# 08_BB_Processor.net
KiCad netlist of a schematic drawn in Altium Designer
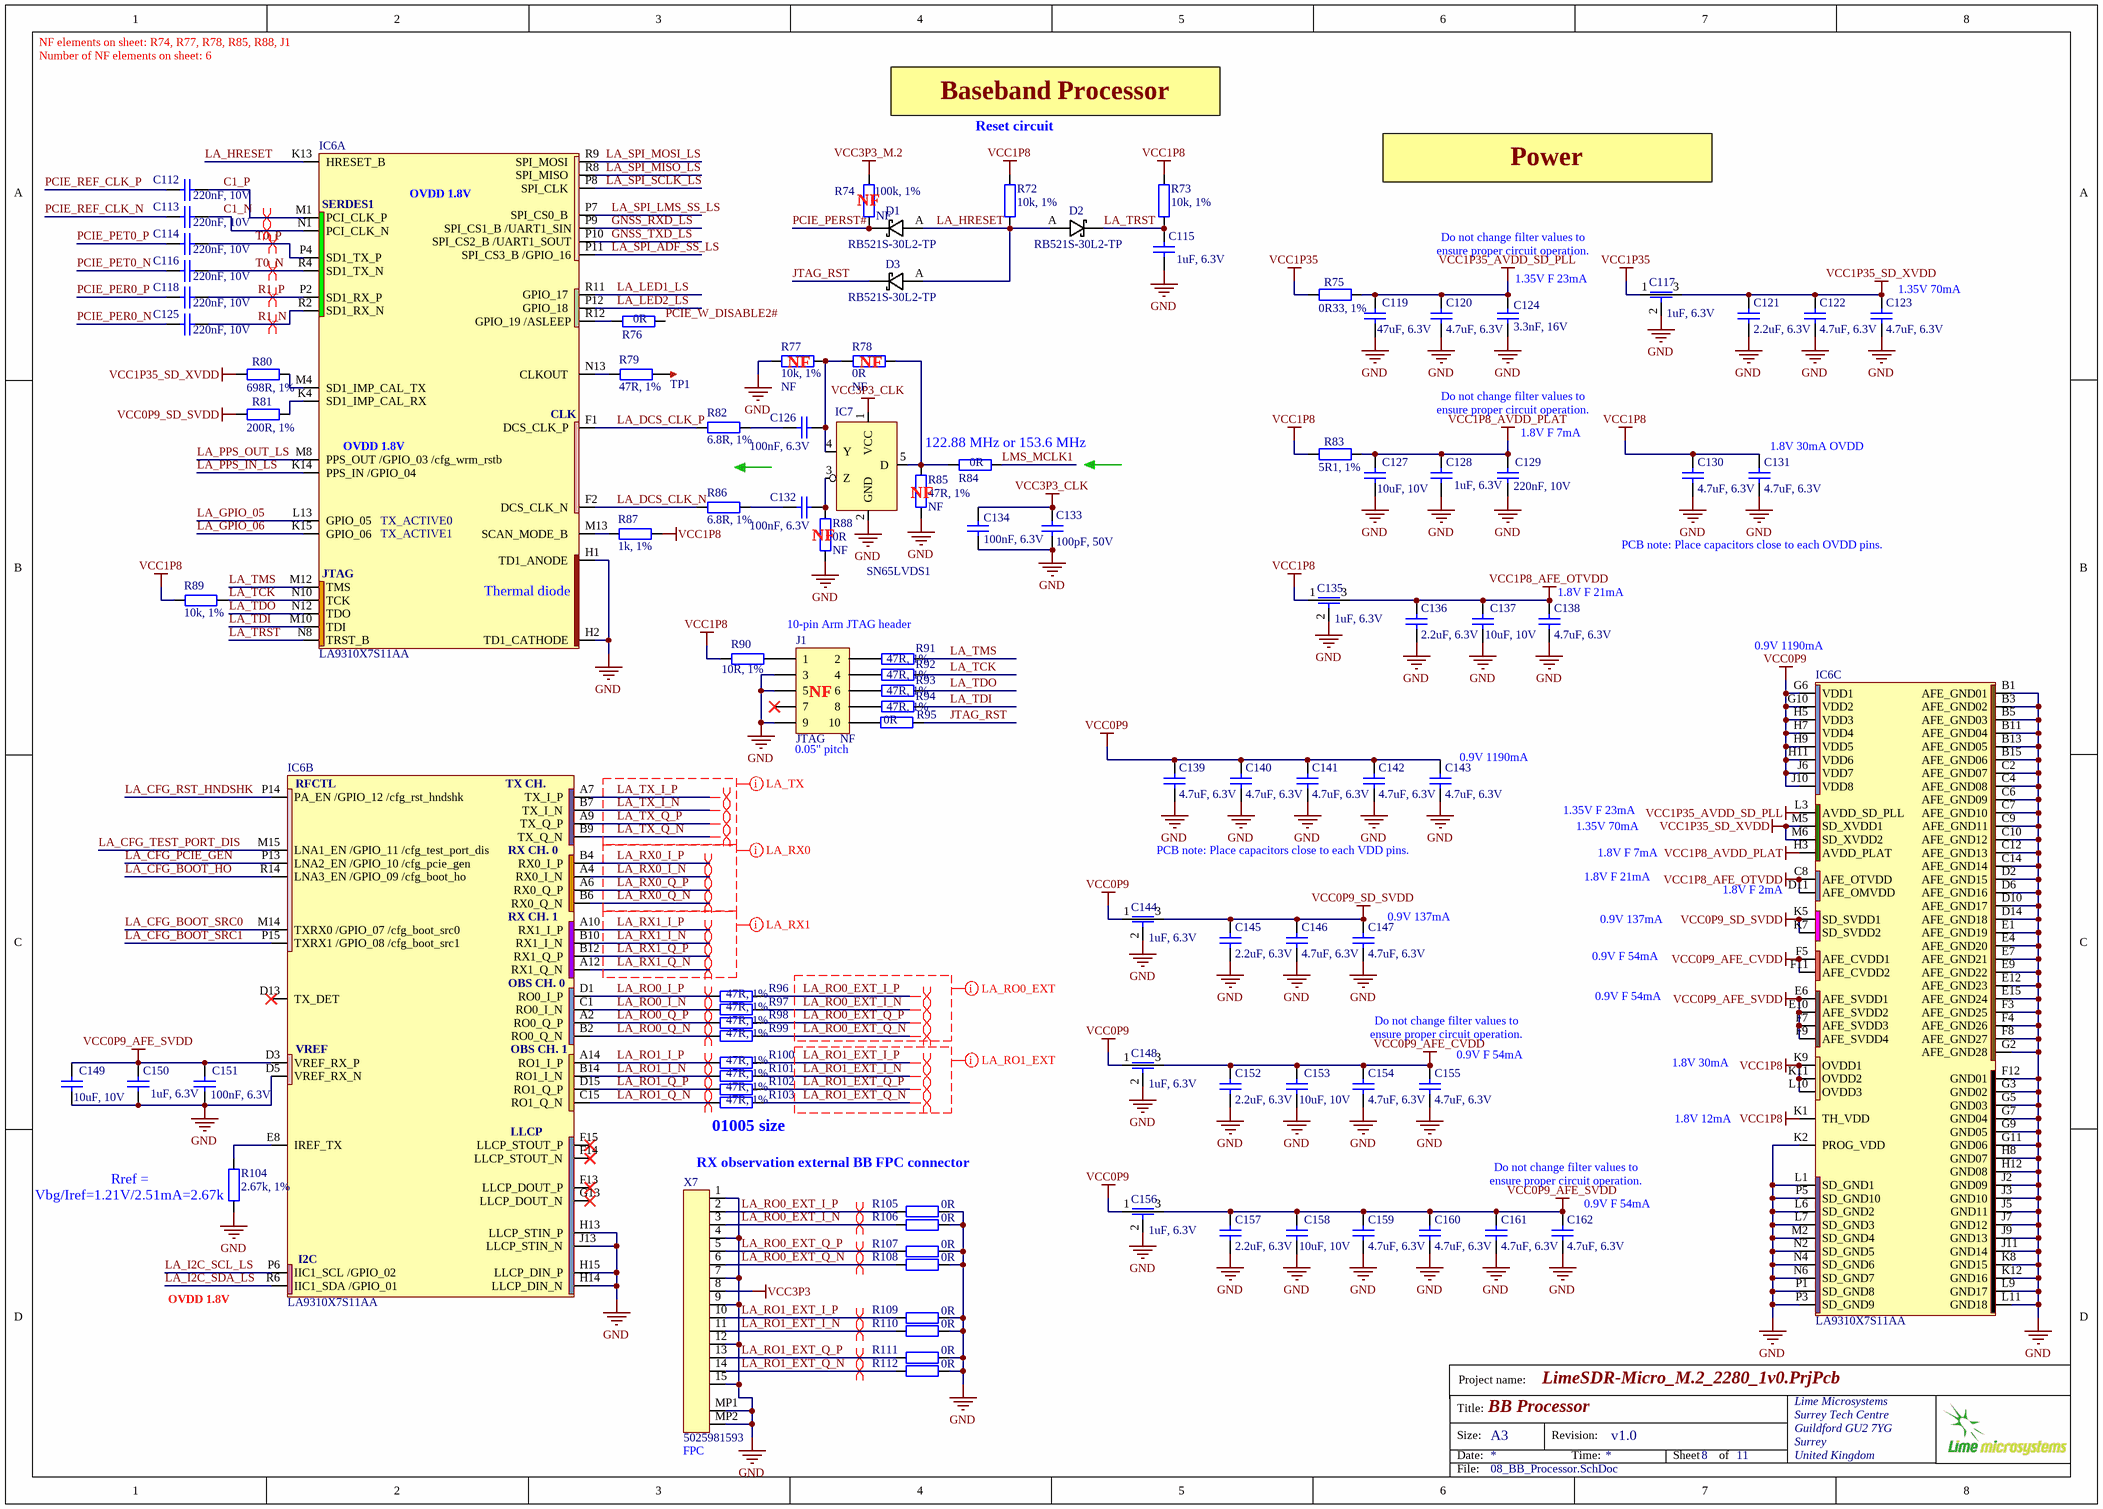
[diagram p0: 08_BB_Processor.SchDoc]

(export (version "E")
  (design (tool "Eeschema 10.0.6"))
  (components
    (comp (ref "C112")
      (value "220nF, 10V")
      (footprint "CAP0201")
      (fields
        (field (name "MANUFACTURER") "Murata")
        (field (name "TOLERANCE") "20%")
        (field (name "VOLTAGE") "10V")
      )
      (libsource (lib "LimeMicroAltiumLib_schLib") (part "Cap_0402"))
    )
    (comp (ref "C113")
      (value "220nF, 10V")
      (footprint "CAP0201")
      (fields
        (field (name "MANUFACTURER") "Murata")
        (field (name "TOLERANCE") "20%")
        (field (name "VOLTAGE") "10V")
      )
      (libsource (lib "LimeMicroAltiumLib_schLib") (part "Cap_0402"))
    )
    (comp (ref "C114")
      (value "220nF, 10V")
      (footprint "CAP0201")
      (fields
        (field (name "MANUFACTURER") "Murata")
        (field (name "TOLERANCE") "20%")
        (field (name "VOLTAGE") "10V")
      )
      (libsource (lib "LimeMicroAltiumLib_schLib") (part "Cap_0402"))
    )
    (comp (ref "C115")
      (value "1uF, 6.3V")
      (footprint "CAP0201")
      (fields (field (name "TOLERANCE") "±20%") (field (name "MANUFACTURER") "TDK Corporation"))
      (libsource (lib "LimeMicroAltiumLib_schLib") (part "Cap_0402"))
    )
    (comp (ref "C116")
      (value "220nF, 10V")
      (footprint "CAP0201")
      (fields
        (field (name "MANUFACTURER") "Murata")
        (field (name "TOLERANCE") "20%")
        (field (name "VOLTAGE") "10V")
      )
      (libsource (lib "LimeMicroAltiumLib_schLib") (part "Cap_0402"))
    )
    (comp (ref "C117")
      (value "1uF, 6.3V")
      (footprint "CAP0603_FEEDTHROUGH")
      (fields (field (name "MANUFACTURER") "TDK"))
      (libsource (lib "LimeMicroAltiumLib_schLib_r01") (part "Cap_feed_through"))
    )
    (comp (ref "C118")
      (value "220nF, 10V")
      (footprint "CAP0201")
      (fields
        (field (name "MANUFACTURER") "Murata")
        (field (name "TOLERANCE") "20%")
        (field (name "VOLTAGE") "10V")
      )
      (libsource (lib "LimeMicroAltiumLib_schLib") (part "Cap_0402"))
    )
    (comp (ref "C119")
      (value "47uF, 6.3V")
      (footprint "CAP0603")
      (fields (field (name "MANUFACTURER") "Murata") (field (name "TOLERANCE") "20%"))
      (libsource (lib "LimeFPGAboard_schLib") (part "Cap_0603"))
    )
    (comp (ref "C120")
      (value "4.7uF, 6.3V")
      (footprint "CAP0201")
      (fields (field (name "MANUFACTURER") "Murata") (field (name "TOLERANCE") "20%"))
      (libsource (lib "LimeMicroAltiumLib_schLib") (part "Cap_0402"))
    )
    (comp (ref "C121")
      (value "2.2uF, 6.3V")
      (footprint "CAP0201")
      (fields (field (name "MANUFACTURER") "Murata") (field (name "TOLERANCE") "20%"))
      (libsource (lib "LimeMicroAltiumLib_schLib") (part "Cap_0402"))
    )
    (comp (ref "C122")
      (value "4.7uF, 6.3V")
      (footprint "CAP0201")
      (fields (field (name "MANUFACTURER") "Murata") (field (name "TOLERANCE") "20%"))
      (libsource (lib "LimeMicroAltiumLib_schLib") (part "Cap_0402"))
    )
    (comp (ref "C123")
      (value "4.7uF, 6.3V")
      (footprint "CAP0201")
      (fields (field (name "MANUFACTURER") "Murata") (field (name "TOLERANCE") "20%"))
      (libsource (lib "LimeMicroAltiumLib_schLib") (part "Cap_0402"))
    )
    (comp (ref "C124")
      (value "3.3nF, 16V")
      (footprint "CAP0201")
      (fields (field (name "MANUFACTURER") "Murata"))
      (libsource (lib "LimeMicroAltiumLib_schLib") (part "Cap_0402"))
    )
    (comp (ref "C125")
      (value "220nF, 10V")
      (footprint "CAP0201")
      (fields
        (field (name "MANUFACTURER") "Murata")
        (field (name "TOLERANCE") "20%")
        (field (name "VOLTAGE") "10V")
      )
      (libsource (lib "LimeMicroAltiumLib_schLib") (part "Cap_0402"))
    )
    (comp (ref "C126")
      (value "100nF, 6.3V")
      (footprint "CAP0201")
      (fields (field (name "MANUFACTURER") "Samsung") (field (name "TOLERANCE") "20%"))
      (libsource (lib "LimeMicroAltiumLib_schLib") (part "Cap_0402"))
    )
    (comp (ref "C127")
      (value "10uF, 10V")
      (footprint "CAP0402")
      (fields (field (name "MANUFACTURER") "Murata"))
      (libsource (lib "LimeFPGAboard_schLib") (part "Cap_0603"))
    )
    (comp (ref "C128")
      (value "1uF, 6.3V")
      (footprint "CAP0201")
      (fields (field (name "TOLERANCE") "±20%") (field (name "MANUFACTURER") "TDK Corporation"))
      (libsource (lib "LimeMicroAltiumLib_schLib") (part "Cap_0402"))
    )
    (comp (ref "C129")
      (value "220nF, 10V")
      (footprint "CAP0201")
      (fields
        (field (name "MANUFACTURER") "Murata")
        (field (name "TOLERANCE") "20%")
        (field (name "VOLTAGE") "10V")
      )
      (libsource (lib "LimeMicroAltiumLib_schLib") (part "Cap_0402"))
    )
    (comp (ref "C130")
      (value "4.7uF, 6.3V")
      (footprint "CAP0201")
      (fields (field (name "MANUFACTURER") "Murata") (field (name "TOLERANCE") "20%"))
      (libsource (lib "LimeMicroAltiumLib_schLib") (part "Cap_0402"))
    )
    (comp (ref "C131")
      (value "4.7uF, 6.3V")
      (footprint "CAP0201")
      (fields (field (name "MANUFACTURER") "Murata") (field (name "TOLERANCE") "20%"))
      (libsource (lib "LimeMicroAltiumLib_schLib") (part "Cap_0402"))
    )
    (comp (ref "C132")
      (value "100nF, 6.3V")
      (footprint "CAP0201")
      (fields (field (name "MANUFACTURER") "Samsung") (field (name "TOLERANCE") "20%"))
      (libsource (lib "LimeMicroAltiumLib_schLib") (part "Cap_0402"))
    )
    (comp (ref "C133")
      (value "100pF, 50V")
      (footprint "CAP0201")
      (fields
        (field (name "MANUFACTURER") "TDK")
        (field (name "TOLERANCE") "5%")
        (field (name "VOLTAGE") "50V")
      )
      (libsource (lib "LimeMicroAltiumLib_schLib") (part "Cap_0402"))
    )
    (comp (ref "C134")
      (value "100nF, 6.3V")
      (footprint "CAP0201")
      (fields (field (name "MANUFACTURER") "Samsung") (field (name "TOLERANCE") "20%"))
      (libsource (lib "LimeMicroAltiumLib_schLib") (part "Cap_0402"))
    )
    (comp (ref "C135")
      (value "1uF, 6.3V")
      (footprint "CAP0603_FEEDTHROUGH")
      (fields (field (name "MANUFACTURER") "TDK"))
      (libsource (lib "LimeMicroAltiumLib_schLib_r01") (part "Cap_feed_through"))
    )
    (comp (ref "C136")
      (value "2.2uF, 6.3V")
      (footprint "CAP0201")
      (fields (field (name "MANUFACTURER") "Murata") (field (name "TOLERANCE") "20%"))
      (libsource (lib "LimeMicroAltiumLib_schLib") (part "Cap_0402"))
    )
    (comp (ref "C137")
      (value "10uF, 10V")
      (footprint "CAP0402")
      (fields (field (name "MANUFACTURER") "Murata"))
      (libsource (lib "LimeFPGAboard_schLib") (part "Cap_0603"))
    )
    (comp (ref "C138")
      (value "4.7uF, 6.3V")
      (footprint "CAP0201")
      (fields (field (name "MANUFACTURER") "Murata") (field (name "TOLERANCE") "20%"))
      (libsource (lib "LimeMicroAltiumLib_schLib") (part "Cap_0402"))
    )
    (comp (ref "C139")
      (value "4.7uF, 6.3V")
      (footprint "CAP0201")
      (fields (field (name "MANUFACTURER") "Murata") (field (name "TOLERANCE") "20%"))
      (libsource (lib "LimeMicroAltiumLib_schLib") (part "Cap_0402"))
    )
    (comp (ref "C140")
      (value "4.7uF, 6.3V")
      (footprint "CAP0201")
      (fields (field (name "MANUFACTURER") "Murata") (field (name "TOLERANCE") "20%"))
      (libsource (lib "LimeMicroAltiumLib_schLib") (part "Cap_0402"))
    )
    (comp (ref "C141")
      (value "4.7uF, 6.3V")
      (footprint "CAP0201")
      (fields (field (name "MANUFACTURER") "Murata") (field (name "TOLERANCE") "20%"))
      (libsource (lib "LimeMicroAltiumLib_schLib") (part "Cap_0402"))
    )
    (comp (ref "C142")
      (value "4.7uF, 6.3V")
      (footprint "CAP0201")
      (fields (field (name "MANUFACTURER") "Murata") (field (name "TOLERANCE") "20%"))
      (libsource (lib "LimeMicroAltiumLib_schLib") (part "Cap_0402"))
    )
    (comp (ref "C143")
      (value "4.7uF, 6.3V")
      (footprint "CAP0201")
      (fields (field (name "MANUFACTURER") "Murata") (field (name "TOLERANCE") "20%"))
      (libsource (lib "LimeMicroAltiumLib_schLib") (part "Cap_0402"))
    )
    (comp (ref "C144")
      (value "1uF, 6.3V")
      (footprint "CAP0603_FEEDTHROUGH")
      (fields (field (name "MANUFACTURER") "TDK"))
      (libsource (lib "LimeMicroAltiumLib_schLib_r01") (part "Cap_feed_through"))
    )
    (comp (ref "C145")
      (value "2.2uF, 6.3V")
      (footprint "CAP0201")
      (fields (field (name "MANUFACTURER") "Murata") (field (name "TOLERANCE") "20%"))
      (libsource (lib "LimeMicroAltiumLib_schLib") (part "Cap_0402"))
    )
    (comp (ref "C146")
      (value "4.7uF, 6.3V")
      (footprint "CAP0201")
      (fields (field (name "MANUFACTURER") "Murata") (field (name "TOLERANCE") "20%"))
      (libsource (lib "LimeMicroAltiumLib_schLib") (part "Cap_0402"))
    )
    (comp (ref "C147")
      (value "4.7uF, 6.3V")
      (footprint "CAP0201")
      (fields (field (name "MANUFACTURER") "Murata") (field (name "TOLERANCE") "20%"))
      (libsource (lib "LimeMicroAltiumLib_schLib") (part "Cap_0402"))
    )
    (comp (ref "C148")
      (value "1uF, 6.3V")
      (footprint "CAP0603_FEEDTHROUGH")
      (fields (field (name "MANUFACTURER") "TDK"))
      (libsource (lib "LimeMicroAltiumLib_schLib_r01") (part "Cap_feed_through"))
    )
    (comp (ref "C149")
      (value "10uF, 10V")
      (footprint "CAP0402")
      (fields (field (name "MANUFACTURER") "Murata"))
      (libsource (lib "LimeFPGAboard_schLib") (part "Cap_0603"))
    )
    (comp (ref "C150")
      (value "1uF, 6.3V")
      (footprint "CAP0201")
      (fields (field (name "TOLERANCE") "±20%") (field (name "MANUFACTURER") "TDK Corporation"))
      (libsource (lib "LimeMicroAltiumLib_schLib") (part "Cap_0402"))
    )
    (comp (ref "C151")
      (value "100nF, 6.3V")
      (footprint "CAP0201")
      (fields (field (name "MANUFACTURER") "Samsung") (field (name "TOLERANCE") "20%"))
      (libsource (lib "LimeMicroAltiumLib_schLib") (part "Cap_0402"))
    )
    (comp (ref "C152")
      (value "2.2uF, 6.3V")
      (footprint "CAP0201")
      (fields (field (name "MANUFACTURER") "Murata") (field (name "TOLERANCE") "20%"))
      (libsource (lib "LimeMicroAltiumLib_schLib") (part "Cap_0402"))
    )
    (comp (ref "C153")
      (value "10uF, 10V")
      (footprint "CAP0402")
      (fields (field (name "MANUFACTURER") "Murata"))
      (libsource (lib "LimeFPGAboard_schLib") (part "Cap_0603"))
    )
    (comp (ref "C154")
      (value "4.7uF, 6.3V")
      (footprint "CAP0201")
      (fields (field (name "MANUFACTURER") "Murata") (field (name "TOLERANCE") "20%"))
      (libsource (lib "LimeMicroAltiumLib_schLib") (part "Cap_0402"))
    )
    (comp (ref "C155")
      (value "4.7uF, 6.3V")
      (footprint "CAP0201")
      (fields (field (name "MANUFACTURER") "Murata") (field (name "TOLERANCE") "20%"))
      (libsource (lib "LimeMicroAltiumLib_schLib") (part "Cap_0402"))
    )
    (comp (ref "C156")
      (value "1uF, 6.3V")
      (footprint "CAP0603_FEEDTHROUGH")
      (fields (field (name "MANUFACTURER") "TDK"))
      (libsource (lib "LimeMicroAltiumLib_schLib_r01") (part "Cap_feed_through"))
    )
    (comp (ref "C157")
      (value "2.2uF, 6.3V")
      (footprint "CAP0201")
      (fields (field (name "MANUFACTURER") "Murata") (field (name "TOLERANCE") "20%"))
      (libsource (lib "LimeMicroAltiumLib_schLib") (part "Cap_0402"))
    )
    (comp (ref "C158")
      (value "10uF, 10V")
      (footprint "CAP0402")
      (fields (field (name "MANUFACTURER") "Murata"))
      (libsource (lib "LimeFPGAboard_schLib") (part "Cap_0603"))
    )
    (comp (ref "C159")
      (value "4.7uF, 6.3V")
      (footprint "CAP0201")
      (fields (field (name "MANUFACTURER") "Murata") (field (name "TOLERANCE") "20%"))
      (libsource (lib "LimeMicroAltiumLib_schLib") (part "Cap_0402"))
    )
    (comp (ref "C160")
      (value "4.7uF, 6.3V")
      (footprint "CAP0201")
      (fields (field (name "MANUFACTURER") "Murata") (field (name "TOLERANCE") "20%"))
      (libsource (lib "LimeMicroAltiumLib_schLib") (part "Cap_0402"))
    )
    (comp (ref "C161")
      (value "4.7uF, 6.3V")
      (footprint "CAP0201")
      (fields (field (name "MANUFACTURER") "Murata") (field (name "TOLERANCE") "20%"))
      (libsource (lib "LimeMicroAltiumLib_schLib") (part "Cap_0402"))
    )
    (comp (ref "C162")
      (value "4.7uF, 6.3V")
      (footprint "CAP0201")
      (fields (field (name "MANUFACTURER") "Murata") (field (name "TOLERANCE") "20%"))
      (libsource (lib "LimeMicroAltiumLib_schLib") (part "Cap_0402"))
    )
    (comp (ref "D1")
      (value "RB521S-30L2-TP")
      (footprint "RB521S-30L2-TP_DFN1006")
      (fields (field (name "MANUFACTURER") "MCC"))
      (libsource (lib "LimeMicroAltiumLib") (part "BAT46JFILM_shottky_diode"))
    )
    (comp (ref "D2")
      (value "RB521S-30L2-TP")
      (footprint "RB521S-30L2-TP_DFN1006")
      (fields (field (name "MANUFACTURER") "MCC"))
      (libsource (lib "LimeMicroAltiumLib") (part "BAT46JFILM_shottky_diode"))
    )
    (comp (ref "D3")
      (value "RB521S-30L2-TP")
      (footprint "RB521S-30L2-TP_DFN1006")
      (fields (field (name "MANUFACTURER") "MCC"))
      (libsource (lib "LimeMicroAltiumLib") (part "BAT46JFILM_shottky_diode"))
    )
    (comp (ref "IC6")
      (value "LA9310X7S11AA")
      (footprint "LA9310X7S11AA")
      (fields (field (name "MANUFACTURER") "NXP Semiconductors"))
      (libsource (lib "LimeMicroAltiumLib") (part "LA9310X7S11AA"))
    )
    (comp (ref "IC7")
      (value "SN65LVDS1")
      (footprint "SOT23-5_NO_SILK")
      (fields (field (name "MANUFACTURER") "TEXAS INSTRUMENTS"))
      (libsource (lib "LimeMicroAltiumLib_schLib") (part "SN65LVDS1"))
    )
    (comp (ref "J1")
      (value "JTAG")
      (footprint "HEADER_5x2_TH_HALF_PITCH")
      (description "Header, 5-Pin, Dual row")
      (fields (field (name "ASSEMBLY INFO") "NF") (field (name "MANUFACTURER") "Adam Equipment"))
      (libsource (lib "LimeMicroAltiumLib") (part "Header 5X2_SWD"))
    )
    (comp (ref "R72")
      (value "10k, 1%")
      (footprint "RES0201")
      (fields (field (name "MANUFACTURER") "Yageo") (field (name "TOLERANCE") "1%"))
      (libsource (lib "LimeFPGAboard_schLib") (part "Res_0402"))
    )
    (comp (ref "R73")
      (value "10k, 1%")
      (footprint "RES0201")
      (fields (field (name "MANUFACTURER") "Yageo") (field (name "TOLERANCE") "1%"))
      (libsource (lib "LimeFPGAboard_schLib") (part "Res_0402"))
    )
    (comp (ref "R74")
      (value "100k, 1%")
      (footprint "RES0201")
      (fields
        (field (name "ASSEMBLY INFO") "NF")
        (field (name "MANUFACTURER") "Yageo")
        (field (name "TOLERANCE") "1%")
      )
      (libsource (lib "LimeFPGAboard_schLib") (part "Res_0402"))
    )
    (comp (ref "R75")
      (value "0R33, 1%")
      (footprint "RES0201")
      (fields (field (name "MANUFACTURER") "Ohmite"))
      (libsource (lib "LimeFPGAboard_schLib") (part "Res_0402"))
    )
    (comp (ref "R76")
      (value "0R")
      (footprint "RES0201")
      (fields (field (name "MANUFACTURER") "Yageo") (field (name "TOLERANCE") "5%"))
      (libsource (lib "LimeFPGAboard_schLib") (part "Res_0402"))
    )
    (comp (ref "R77")
      (value "10k, 1%")
      (footprint "RES0201")
      (fields
        (field (name "ASSEMBLY INFO") "NF")
        (field (name "MANUFACTURER") "Yageo")
        (field (name "TOLERANCE") "1%")
      )
      (libsource (lib "LimeFPGAboard_schLib") (part "Res_0402"))
    )
    (comp (ref "R78")
      (value "0R")
      (footprint "RES0201")
      (fields
        (field (name "ASSEMBLY INFO") "NF")
        (field (name "MANUFACTURER") "Yageo")
        (field (name "TOLERANCE") "5%")
      )
      (libsource (lib "LimeFPGAboard_schLib") (part "Res_0402"))
    )
    (comp (ref "R79")
      (value "47R, 1%")
      (footprint "RES0201")
      (fields (field (name "MANUFACTURER") "Yageo") (field (name "TOLERANCE") "1%"))
      (libsource (lib "LimeFPGAboard_schLib") (part "Res_0402"))
    )
    (comp (ref "R80")
      (value "698R, 1%")
      (footprint "RES0201")
      (fields (field (name "MANUFACTURER") "Yageo") (field (name "TOLERANCE") "1%"))
      (libsource (lib "LimeFPGAboard_schLib") (part "Res_0402"))
    )
    (comp (ref "R81")
      (value "200R, 1%")
      (footprint "RES0201")
      (fields (field (name "MANUFACTURER") "Yageo") (field (name "TOLERANCE") "1%"))
      (libsource (lib "LimeFPGAboard_schLib") (part "Res_0402"))
    )
    (comp (ref "R82")
      (value "6.8R, 1%")
      (footprint "RES0201")
      (fields (field (name "MANUFACTURER") "Yageo") (field (name "TOLERANCE") "1%"))
      (libsource (lib "LimeMicroAltiumLib_schLib") (part "Res_0402"))
    )
    (comp (ref "R83")
      (value "5R1, 1%")
      (footprint "RES0201")
      (fields (field (name "MANUFACTURER") "Yageo"))
      (libsource (lib "LimeFPGAboard_schLib") (part "Res_0402"))
    )
    (comp (ref "R84")
      (value "0R")
      (footprint "RES0201")
      (fields (field (name "MANUFACTURER") "Yageo") (field (name "TOLERANCE") "5%"))
      (libsource (lib "LimeFPGAboard_schLib") (part "Res_0402"))
    )
    (comp (ref "R85")
      (value "47R, 1%")
      (footprint "RES0201")
      (fields
        (field (name "ASSEMBLY INFO") "NF")
        (field (name "MANUFACTURER") "Yageo")
        (field (name "TOLERANCE") "1%")
      )
      (libsource (lib "LimeFPGAboard_schLib") (part "Res_0402"))
    )
    (comp (ref "R86")
      (value "6.8R, 1%")
      (footprint "RES0201")
      (fields (field (name "MANUFACTURER") "Yageo") (field (name "TOLERANCE") "1%"))
      (libsource (lib "LimeMicroAltiumLib_schLib") (part "Res_0402"))
    )
    (comp (ref "R87")
      (value "1k, 1%")
      (footprint "RES0201")
      (fields (field (name "MANUFACTURER") "Yageo") (field (name "TOLERANCE") "1%"))
      (libsource (lib "LimeMicroAltiumLib_schLib") (part "Res_0402"))
    )
    (comp (ref "R88")
      (value "0R")
      (footprint "RES0201")
      (fields
        (field (name "ASSEMBLY INFO") "NF")
        (field (name "MANUFACTURER") "Yageo")
        (field (name "TOLERANCE") "5%")
      )
      (libsource (lib "LimeFPGAboard_schLib") (part "Res_0402"))
    )
    (comp (ref "R89")
      (value "10k, 1%")
      (footprint "RES0201")
      (fields (field (name "MANUFACTURER") "Yageo") (field (name "TOLERANCE") "1%"))
      (libsource (lib "LimeFPGAboard_schLib") (part "Res_0402"))
    )
    (comp (ref "R90")
      (value "10R, 1%")
      (footprint "RES0201")
      (fields
        (field (name "MANUFACTURER") "Panasonic Electronic Components")
        (field (name "TOLERANCE") "±1%")
      )
      (libsource (lib "LimeMicroAltiumLib_schLib") (part "Res_0402"))
    )
    (comp (ref "R91")
      (value "47R, 1%")
      (footprint "RES0201")
      (fields (field (name "MANUFACTURER") "Yageo") (field (name "TOLERANCE") "1%"))
      (libsource (lib "LimeFPGAboard_schLib") (part "Res_0402"))
    )
    (comp (ref "R92")
      (value "47R, 1%")
      (footprint "RES0201")
      (fields (field (name "MANUFACTURER") "Yageo") (field (name "TOLERANCE") "1%"))
      (libsource (lib "LimeFPGAboard_schLib") (part "Res_0402"))
    )
    (comp (ref "R93")
      (value "47R, 1%")
      (footprint "RES0201")
      (fields (field (name "MANUFACTURER") "Yageo") (field (name "TOLERANCE") "1%"))
      (libsource (lib "LimeFPGAboard_schLib") (part "Res_0402"))
    )
    (comp (ref "R94")
      (value "47R, 1%")
      (footprint "RES0201")
      (fields (field (name "MANUFACTURER") "Yageo") (field (name "TOLERANCE") "1%"))
      (libsource (lib "LimeFPGAboard_schLib") (part "Res_0402"))
    )
    (comp (ref "R95")
      (value "0R")
      (footprint "RES0201")
      (fields (field (name "MANUFACTURER") "Yageo") (field (name "TOLERANCE") "5%"))
      (libsource (lib "LimeFPGAboard_schLib") (part "Res_0402"))
    )
    (comp (ref "R96")
      (value "47R, 1%")
      (footprint "RES01005")
      (fields (field (name "MANUFACTURER") "Yageo") (field (name "TOLERANCE") "1%"))
      (libsource (lib "LimeFPGAboard_schLib") (part "Res_0402"))
    )
    (comp (ref "R97")
      (value "47R, 1%")
      (footprint "RES01005")
      (fields (field (name "MANUFACTURER") "Yageo") (field (name "TOLERANCE") "1%"))
      (libsource (lib "LimeFPGAboard_schLib") (part "Res_0402"))
    )
    (comp (ref "R98")
      (value "47R, 1%")
      (footprint "RES01005")
      (fields (field (name "MANUFACTURER") "Yageo") (field (name "TOLERANCE") "1%"))
      (libsource (lib "LimeFPGAboard_schLib") (part "Res_0402"))
    )
    (comp (ref "R99")
      (value "47R, 1%")
      (footprint "RES01005")
      (fields (field (name "MANUFACTURER") "Yageo") (field (name "TOLERANCE") "1%"))
      (libsource (lib "LimeFPGAboard_schLib") (part "Res_0402"))
    )
    (comp (ref "R100")
      (value "47R, 1%")
      (footprint "RES01005")
      (fields (field (name "MANUFACTURER") "Yageo") (field (name "TOLERANCE") "1%"))
      (libsource (lib "LimeFPGAboard_schLib") (part "Res_0402"))
    )
    (comp (ref "R101")
      (value "47R, 1%")
      (footprint "RES01005")
      (fields (field (name "MANUFACTURER") "Yageo") (field (name "TOLERANCE") "1%"))
      (libsource (lib "LimeFPGAboard_schLib") (part "Res_0402"))
    )
    (comp (ref "R102")
      (value "47R, 1%")
      (footprint "RES01005")
      (fields (field (name "MANUFACTURER") "Yageo") (field (name "TOLERANCE") "1%"))
      (libsource (lib "LimeFPGAboard_schLib") (part "Res_0402"))
    )
    (comp (ref "R103")
      (value "47R, 1%")
      (footprint "RES01005")
      (fields (field (name "MANUFACTURER") "Yageo") (field (name "TOLERANCE") "1%"))
      (libsource (lib "LimeFPGAboard_schLib") (part "Res_0402"))
    )
    (comp (ref "R104")
      (value "2.67k, 1%")
      (footprint "RES0201")
      (fields (field (name "MANUFACTURER") "Stackpole Electronics") (field (name "TOLERANCE") "1%"))
      (libsource (lib "LimeFPGAboard_schLib") (part "Res_0402"))
    )
    (comp (ref "R105")
      (value "0R")
      (footprint "RES01005")
      (fields (field (name "MANUFACTURER") "Panasonic") (field (name "TOLERANCE") "5%"))
      (libsource (lib "LimeFPGAboard_schLib") (part "Res_0402"))
    )
    (comp (ref "R106")
      (value "0R")
      (footprint "RES01005")
      (fields (field (name "MANUFACTURER") "Panasonic") (field (name "TOLERANCE") "5%"))
      (libsource (lib "LimeFPGAboard_schLib") (part "Res_0402"))
    )
    (comp (ref "R107")
      (value "0R")
      (footprint "RES01005")
      (fields (field (name "MANUFACTURER") "Panasonic") (field (name "TOLERANCE") "5%"))
      (libsource (lib "LimeFPGAboard_schLib") (part "Res_0402"))
    )
    (comp (ref "R108")
      (value "0R")
      (footprint "RES01005")
      (fields (field (name "MANUFACTURER") "Panasonic") (field (name "TOLERANCE") "5%"))
      (libsource (lib "LimeFPGAboard_schLib") (part "Res_0402"))
    )
    (comp (ref "R109")
      (value "0R")
      (footprint "RES01005")
      (fields (field (name "MANUFACTURER") "Panasonic") (field (name "TOLERANCE") "5%"))
      (libsource (lib "LimeFPGAboard_schLib") (part "Res_0402"))
    )
    (comp (ref "R110")
      (value "0R")
      (footprint "RES01005")
      (fields (field (name "MANUFACTURER") "Panasonic") (field (name "TOLERANCE") "5%"))
      (libsource (lib "LimeFPGAboard_schLib") (part "Res_0402"))
    )
    (comp (ref "R111")
      (value "0R")
      (footprint "RES01005")
      (fields (field (name "MANUFACTURER") "Panasonic") (field (name "TOLERANCE") "5%"))
      (libsource (lib "LimeFPGAboard_schLib") (part "Res_0402"))
    )
    (comp (ref "R112")
      (value "0R")
      (footprint "RES01005")
      (fields (field (name "MANUFACTURER") "Panasonic") (field (name "TOLERANCE") "5%"))
      (libsource (lib "LimeFPGAboard_schLib") (part "Res_0402"))
    )
    (comp (ref "TP1")
      (value "TESTPOINT_PAD")
      (footprint "TP_PAD_1MM")
      (description "Test Point PCB mount Miniature White")
      (libsource (lib "LimeMicroAltiumLib_schLib_r04") (part "TESTPOINT_PAD"))
    )
    (comp (ref "X7")
      (value "5025981593")
      (footprint "5025981593_FPC_connector")
      (fields (field (name "MANUFACTURER") "Molex"))
      (libsource (lib "LimeMicroAltiumLib_schLib_r04") (part "5025981593_FPC_connector"))
    )
  )
  (nets
    (net (code "1") (name "/C1_N") (class "Default")
      (node (ref "C113") (pin "2") (pinfunction "2_2") (pintype "passive"))
      (node (ref "IC6") (pin "N1") (pinfunction "PCI_CLK_N_N1") (pintype "power_in"))
    )
    (net (code "2") (name "/C1_P") (class "Default")
      (node (ref "C112") (pin "2") (pinfunction "2_2") (pintype "passive"))
      (node (ref "IC6") (pin "M1") (pinfunction "PCI_CLK_P_M1") (pintype "power_in"))
    )
    (net (code "3") (name "/GNSS_RXD_LS") (class "Default")
      (node (ref "IC6") (pin "P9") (pinfunction "SPI_CS1_B_/UART1_SIN_P9") (pintype "power_in"))
    )
    (net (code "4") (name "/GNSS_TXD_LS") (class "Default")
      (node (ref "IC6") (pin "P10") (pinfunction "SPI_CS2_B_/UART1_SOUT_P10") (pintype "power_in"))
    )
    (net (code "5") (name "/JTAG_RST") (class "Default")
      (node (ref "D3") (pin "C") (pinfunction "C_C") (pintype "passive"))
      (node (ref "R95") (pin "2") (pinfunction "2_2") (pintype "passive"))
    )
    (net (code "6") (name "/LA_CFG_BOOT_HO") (class "Default")
      (node (ref "IC6") (pin "R14") (pinfunction "LNA3_EN_/GPIO_09_/cfg_boot_ho_R14") (pintype "power_in"))
    )
    (net (code "7") (name "/LA_CFG_BOOT_SRC0") (class "Default")
      (node (ref "IC6") (pin "M14") (pinfunction "TXRX0_/GPIO_07_/cfg_boot_src0_M14") (pintype "power_in"))
    )
    (net (code "8") (name "/LA_CFG_BOOT_SRC1") (class "Default")
      (node (ref "IC6") (pin "P15") (pinfunction "TXRX1_/GPIO_08_/cfg_boot_src1_P15") (pintype "power_in"))
    )
    (net (code "9") (name "/LA_CFG_PCIE_GEN") (class "Default")
      (node (ref "IC6") (pin "P13") (pinfunction "LNA2_EN_/GPIO_10_/cfg_pcie_gen_P13") (pintype "power_in"))
    )
    (net (code "10") (name "/LA_CFG_RST_HNDSHK") (class "Default")
      (node (ref "IC6") (pin "P14") (pinfunction "PA_EN_/GPIO_12_/cfg_rst_hndshk_P14") (pintype "power_in"))
    )
    (net (code "11") (name "/LA_CFG_TEST_PORT_DIS") (class "Default")
      (node (ref "IC6") (pin "M15") (pinfunction "LNA1_EN_/GPIO_11_/cfg_test_port_dis_M15") (pintype "power_in"))
    )
    (net (code "12") (name "/LA_DCS_CLK_N") (class "Default")
      (node (ref "IC6") (pin "F2") (pinfunction "DCS_CLK_N_F2") (pintype "power_in"))
      (node (ref "R86") (pin "2") (pinfunction "2_2") (pintype "passive"))
    )
    (net (code "13") (name "/LA_DCS_CLK_P") (class "Default")
      (node (ref "IC6") (pin "F1") (pinfunction "DCS_CLK_P_F1") (pintype "power_in"))
      (node (ref "R82") (pin "2") (pinfunction "2_2") (pintype "passive"))
    )
    (net (code "14") (name "/LA_GPIO_05") (class "Default")
      (node (ref "IC6") (pin "L13") (pinfunction "GPIO_05_L13") (pintype "power_in"))
    )
    (net (code "15") (name "/LA_GPIO_06") (class "Default")
      (node (ref "IC6") (pin "K15") (pinfunction "GPIO_06_K15") (pintype "power_in"))
    )
    (net (code "16") (name "/LA_HRESET") (class "Default")
      (node (ref "D1") (pin "A") (pinfunction "A_A") (pintype "passive"))
      (node (ref "D2") (pin "A") (pinfunction "A_A") (pintype "passive"))
      (node (ref "D3") (pin "A") (pinfunction "A_A") (pintype "passive"))
      (node (ref "IC6") (pin "K13") (pinfunction "HRESET_B_K13") (pintype "power_in"))
      (node (ref "R72") (pin "2") (pinfunction "2_2") (pintype "passive"))
    )
    (net (code "17") (name "/LA_I2C_SCL_LS") (class "Default")
      (node (ref "IC6") (pin "P6") (pinfunction "IIC1_SCL_/GPIO_02_P6") (pintype "power_in"))
    )
    (net (code "18") (name "/LA_I2C_SDA_LS") (class "Default")
      (node (ref "IC6") (pin "R6") (pinfunction "IIC1_SDA_/GPIO_01_R6") (pintype "power_in"))
    )
    (net (code "19") (name "/LA_LED1_LS") (class "Default")
      (node (ref "IC6") (pin "R11") (pinfunction "GPIO_17_R11") (pintype "power_in"))
    )
    (net (code "20") (name "/LA_LED2_LS") (class "Default")
      (node (ref "IC6") (pin "P12") (pinfunction "GPIO_18_P12") (pintype "power_in"))
    )
    (net (code "21") (name "/LA_PPS_IN_LS") (class "Default")
      (node (ref "IC6") (pin "K14") (pinfunction "PPS_IN_/GPIO_04_K14") (pintype "power_in"))
    )
    (net (code "22") (name "/LA_PPS_OUT_LS") (class "Default")
      (node (ref "IC6") (pin "M8") (pinfunction "PPS_OUT_/GPIO_03_/cfg_wrm_rstb_M8") (pintype "power_in"))
    )
    (net (code "23") (name "/LA_RO0_EXT_I_N") (class "Default")
      (node (ref "R106") (pin "1") (pinfunction "1_1") (pintype "passive"))
      (node (ref "R97") (pin "2") (pinfunction "2_2") (pintype "passive"))
      (node (ref "X7") (pin "3") (pinfunction "3_3") (pintype "passive"))
    )
    (net (code "24") (name "/LA_RO0_EXT_I_P") (class "Default")
      (node (ref "R105") (pin "1") (pinfunction "1_1") (pintype "passive"))
      (node (ref "R96") (pin "2") (pinfunction "2_2") (pintype "passive"))
      (node (ref "X7") (pin "2") (pinfunction "2_2") (pintype "passive"))
    )
    (net (code "25") (name "/LA_RO0_EXT_Q_N") (class "Default")
      (node (ref "R108") (pin "1") (pinfunction "1_1") (pintype "passive"))
      (node (ref "R99") (pin "2") (pinfunction "2_2") (pintype "passive"))
      (node (ref "X7") (pin "6") (pinfunction "6_6") (pintype "passive"))
    )
    (net (code "26") (name "/LA_RO0_EXT_Q_P") (class "Default")
      (node (ref "R107") (pin "1") (pinfunction "1_1") (pintype "passive"))
      (node (ref "R98") (pin "2") (pinfunction "2_2") (pintype "passive"))
      (node (ref "X7") (pin "5") (pinfunction "5_5") (pintype "passive"))
    )
    (net (code "27") (name "/LA_RO0_I_N") (class "Default")
      (node (ref "IC6") (pin "C1") (pinfunction "RO0_I_N_C1") (pintype "power_in"))
      (node (ref "R97") (pin "1") (pinfunction "1_1") (pintype "passive"))
    )
    (net (code "28") (name "/LA_RO0_I_P") (class "Default")
      (node (ref "IC6") (pin "D1") (pinfunction "RO0_I_P_D1") (pintype "power_in"))
      (node (ref "R96") (pin "1") (pinfunction "1_1") (pintype "passive"))
    )
    (net (code "29") (name "/LA_RO0_Q_N") (class "Default")
      (node (ref "IC6") (pin "B2") (pinfunction "RO0_Q_N_B2") (pintype "power_in"))
      (node (ref "R99") (pin "1") (pinfunction "1_1") (pintype "passive"))
    )
    (net (code "30") (name "/LA_RO0_Q_P") (class "Default")
      (node (ref "IC6") (pin "A2") (pinfunction "RO0_Q_P_A2") (pintype "power_in"))
      (node (ref "R98") (pin "1") (pinfunction "1_1") (pintype "passive"))
    )
    (net (code "31") (name "/LA_RO1_EXT_I_N") (class "Default")
      (node (ref "R101") (pin "2") (pinfunction "2_2") (pintype "passive"))
      (node (ref "R110") (pin "1") (pinfunction "1_1") (pintype "passive"))
      (node (ref "X7") (pin "11") (pinfunction "11_11") (pintype "passive"))
    )
    (net (code "32") (name "/LA_RO1_EXT_I_P") (class "Default")
      (node (ref "R100") (pin "2") (pinfunction "2_2") (pintype "passive"))
      (node (ref "R109") (pin "1") (pinfunction "1_1") (pintype "passive"))
      (node (ref "X7") (pin "10") (pinfunction "10_10") (pintype "passive"))
    )
    (net (code "33") (name "/LA_RO1_EXT_Q_N") (class "Default")
      (node (ref "R103") (pin "2") (pinfunction "2_2") (pintype "passive"))
      (node (ref "R112") (pin "1") (pinfunction "1_1") (pintype "passive"))
      (node (ref "X7") (pin "14") (pinfunction "14_14") (pintype "passive"))
    )
    (net (code "34") (name "/LA_RO1_EXT_Q_P") (class "Default")
      (node (ref "R102") (pin "2") (pinfunction "2_2") (pintype "passive"))
      (node (ref "R111") (pin "1") (pinfunction "1_1") (pintype "passive"))
      (node (ref "X7") (pin "13") (pinfunction "13_13") (pintype "passive"))
    )
    (net (code "35") (name "/LA_RO1_I_N") (class "Default")
      (node (ref "IC6") (pin "B14") (pinfunction "RO1_I_N_B14") (pintype "power_in"))
      (node (ref "R101") (pin "1") (pinfunction "1_1") (pintype "passive"))
    )
    (net (code "36") (name "/LA_RO1_I_P") (class "Default")
      (node (ref "IC6") (pin "A14") (pinfunction "RO1_I_P_A14") (pintype "power_in"))
      (node (ref "R100") (pin "1") (pinfunction "1_1") (pintype "passive"))
    )
    (net (code "37") (name "/LA_RO1_Q_N") (class "Default")
      (node (ref "IC6") (pin "C15") (pinfunction "RO1_Q_N_C15") (pintype "power_in"))
      (node (ref "R103") (pin "1") (pinfunction "1_1") (pintype "passive"))
    )
    (net (code "38") (name "/LA_RO1_Q_P") (class "Default")
      (node (ref "IC6") (pin "D15") (pinfunction "RO1_Q_P_D15") (pintype "power_in"))
      (node (ref "R102") (pin "1") (pinfunction "1_1") (pintype "passive"))
    )
    (net (code "39") (name "/LA_RX0_I_N") (class "Default")
      (node (ref "IC6") (pin "A4") (pinfunction "RX0_I_N_A4") (pintype "power_in"))
    )
    (net (code "40") (name "/LA_RX0_I_P") (class "Default")
      (node (ref "IC6") (pin "B4") (pinfunction "RX0_I_P_B4") (pintype "power_in"))
    )
    (net (code "41") (name "/LA_RX0_Q_N") (class "Default")
      (node (ref "IC6") (pin "B6") (pinfunction "RX0_Q_N_B6") (pintype "power_in"))
    )
    (net (code "42") (name "/LA_RX0_Q_P") (class "Default")
      (node (ref "IC6") (pin "A6") (pinfunction "RX0_Q_P_A6") (pintype "power_in"))
    )
    (net (code "43") (name "/LA_RX1_I_N") (class "Default")
      (node (ref "IC6") (pin "B10") (pinfunction "RX1_I_N_B10") (pintype "power_in"))
    )
    (net (code "44") (name "/LA_RX1_I_P") (class "Default")
      (node (ref "IC6") (pin "A10") (pinfunction "RX1_I_P_A10") (pintype "power_in"))
    )
    (net (code "45") (name "/LA_RX1_Q_N") (class "Default")
      (node (ref "IC6") (pin "A12") (pinfunction "RX1_Q_N_A12") (pintype "power_in"))
    )
    (net (code "46") (name "/LA_RX1_Q_P") (class "Default")
      (node (ref "IC6") (pin "B12") (pinfunction "RX1_Q_P_B12") (pintype "power_in"))
    )
    (net (code "47") (name "/LA_SPI_ADF_SS_LS") (class "Default")
      (node (ref "IC6") (pin "P11") (pinfunction "SPI_CS3_B_/GPIO_16_P11") (pintype "power_in"))
    )
    (net (code "48") (name "/LA_SPI_LMS_SS_LS") (class "Default")
      (node (ref "IC6") (pin "P7") (pinfunction "SPI_CS0_B_P7") (pintype "power_in"))
    )
    (net (code "49") (name "/LA_SPI_MISO_LS") (class "Default")
      (node (ref "IC6") (pin "R8") (pinfunction "SPI_MISO_R8") (pintype "power_in"))
    )
    (net (code "50") (name "/LA_SPI_MOSI_LS") (class "Default")
      (node (ref "IC6") (pin "R9") (pinfunction "SPI_MOSI_R9") (pintype "power_in"))
    )
    (net (code "51") (name "/LA_SPI_SCLK_LS") (class "Default")
      (node (ref "IC6") (pin "P8") (pinfunction "SPI_CLK_P8") (pintype "power_in"))
    )
    (net (code "52") (name "/LA_TCK") (class "Default")
      (node (ref "IC6") (pin "N10") (pinfunction "TCK_N10") (pintype "power_in"))
      (node (ref "R89") (pin "2") (pinfunction "2_2") (pintype "passive"))
      (node (ref "R92") (pin "1") (pinfunction "1_1") (pintype "passive"))
    )
    (net (code "53") (name "/LA_TDI") (class "Default")
      (node (ref "IC6") (pin "M10") (pinfunction "TDI_M10") (pintype "power_in"))
      (node (ref "R94") (pin "1") (pinfunction "1_1") (pintype "passive"))
    )
    (net (code "54") (name "/LA_TDO") (class "Default")
      (node (ref "IC6") (pin "N12") (pinfunction "TDO_N12") (pintype "power_in"))
      (node (ref "R93") (pin "1") (pinfunction "1_1") (pintype "passive"))
    )
    (net (code "55") (name "/LA_TMS") (class "Default")
      (node (ref "IC6") (pin "M12") (pinfunction "TMS_M12") (pintype "power_in"))
      (node (ref "R91") (pin "1") (pinfunction "1_1") (pintype "passive"))
    )
    (net (code "56") (name "/LA_TRST") (class "Default")
      (node (ref "C115") (pin "1") (pinfunction "1_1") (pintype "passive"))
      (node (ref "D2") (pin "C") (pinfunction "C_C") (pintype "passive"))
      (node (ref "IC6") (pin "N8") (pinfunction "TRST_B_N8") (pintype "power_in"))
      (node (ref "R73") (pin "2") (pinfunction "2_2") (pintype "passive"))
    )
    (net (code "57") (name "/LA_TX_I_N") (class "Default")
      (node (ref "IC6") (pin "B7") (pinfunction "TX_I_N_B7") (pintype "power_in"))
    )
    (net (code "58") (name "/LA_TX_I_P") (class "Default")
      (node (ref "IC6") (pin "A7") (pinfunction "TX_I_P_A7") (pintype "power_in"))
    )
    (net (code "59") (name "/LA_TX_Q_N") (class "Default")
      (node (ref "IC6") (pin "B9") (pinfunction "TX_Q_N_B9") (pintype "power_in"))
    )
    (net (code "60") (name "/LA_TX_Q_P") (class "Default")
      (node (ref "IC6") (pin "A9") (pinfunction "TX_Q_P_A9") (pintype "power_in"))
    )
    (net (code "61") (name "/LMS_MCLK1") (class "Default")
      (node (ref "R84") (pin "1") (pinfunction "1_1") (pintype "passive"))
    )
    (net (code "62") (name "/PCIE_PER0_N") (class "Default")
      (node (ref "C125") (pin "1") (pinfunction "1_1") (pintype "passive"))
    )
    (net (code "63") (name "/PCIE_PER0_P") (class "Default")
      (node (ref "C118") (pin "1") (pinfunction "1_1") (pintype "passive"))
    )
    (net (code "64") (name "/PCIE_PERST#") (class "Default")
      (node (ref "D1") (pin "C") (pinfunction "C_C") (pintype "passive"))
      (node (ref "R74") (pin "2") (pinfunction "2_2") (pintype "passive"))
    )
    (net (code "65") (name "/PCIE_PET0_N") (class "Default")
      (node (ref "C116") (pin "1") (pinfunction "1_1") (pintype "passive"))
    )
    (net (code "66") (name "/PCIE_PET0_P") (class "Default")
      (node (ref "C114") (pin "1") (pinfunction "1_1") (pintype "passive"))
    )
    (net (code "67") (name "/PCIE_REF_CLK_N") (class "Default")
      (node (ref "C113") (pin "1") (pinfunction "1_1") (pintype "passive"))
    )
    (net (code "68") (name "/PCIE_REF_CLK_P") (class "Default")
      (node (ref "C112") (pin "1") (pinfunction "1_1") (pintype "passive"))
    )
    (net (code "69") (name "/PCIE_W_DISABLE2#") (class "Default")
      (node (ref "R76") (pin "1") (pinfunction "1_1") (pintype "passive"))
    )
    (net (code "70") (name "/R1_N") (class "Default")
      (node (ref "C125") (pin "2") (pinfunction "2_2") (pintype "passive"))
      (node (ref "IC6") (pin "R2") (pinfunction "SD1_RX_N_R2") (pintype "power_in"))
    )
    (net (code "71") (name "/R1_P") (class "Default")
      (node (ref "C118") (pin "2") (pinfunction "2_2") (pintype "passive"))
      (node (ref "IC6") (pin "P2") (pinfunction "SD1_RX_P_P2") (pintype "power_in"))
    )
    (net (code "72") (name "/T0_N") (class "Default")
      (node (ref "C116") (pin "2") (pinfunction "2_2") (pintype "passive"))
      (node (ref "IC6") (pin "R4") (pinfunction "SD1_TX_N_R4") (pintype "power_in"))
    )
    (net (code "73") (name "/T0_P") (class "Default")
      (node (ref "C114") (pin "2") (pinfunction "2_2") (pintype "passive"))
      (node (ref "IC6") (pin "P4") (pinfunction "SD1_TX_P_P4") (pintype "power_in"))
    )
    (net (code "74") (name "GND") (class "Default")
      (node (ref "C115") (pin "2") (pinfunction "2_2") (pintype "passive"))
      (node (ref "C117") (pin "2") (pinfunction "2_2") (pintype "passive"))
      (node (ref "C119") (pin "1") (pinfunction "1_1") (pintype "passive"))
      (node (ref "C120") (pin "1") (pinfunction "1_1") (pintype "passive"))
      (node (ref "C121") (pin "1") (pinfunction "1_1") (pintype "passive"))
      (node (ref "C122") (pin "1") (pinfunction "1_1") (pintype "passive"))
      (node (ref "C123") (pin "1") (pinfunction "1_1") (pintype "passive"))
      (node (ref "C124") (pin "2") (pinfunction "2_2") (pintype "passive"))
      (node (ref "C127") (pin "1") (pinfunction "1_1") (pintype "passive"))
      (node (ref "C128") (pin "2") (pinfunction "2_2") (pintype "passive"))
      (node (ref "C129") (pin "2") (pinfunction "2_2") (pintype "passive"))
      (node (ref "C130") (pin "1") (pinfunction "1_1") (pintype "passive"))
      (node (ref "C131") (pin "1") (pinfunction "1_1") (pintype "passive"))
      (node (ref "C133") (pin "1") (pinfunction "1_1") (pintype "passive"))
      (node (ref "C134") (pin "2") (pinfunction "2_2") (pintype "passive"))
      (node (ref "C135") (pin "2") (pinfunction "2_2") (pintype "passive"))
      (node (ref "C136") (pin "1") (pinfunction "1_1") (pintype "passive"))
      (node (ref "C137") (pin "1") (pinfunction "1_1") (pintype "passive"))
      (node (ref "C138") (pin "1") (pinfunction "1_1") (pintype "passive"))
      (node (ref "C139") (pin "1") (pinfunction "1_1") (pintype "passive"))
      (node (ref "C140") (pin "1") (pinfunction "1_1") (pintype "passive"))
      (node (ref "C141") (pin "1") (pinfunction "1_1") (pintype "passive"))
      (node (ref "C142") (pin "1") (pinfunction "1_1") (pintype "passive"))
      (node (ref "C143") (pin "1") (pinfunction "1_1") (pintype "passive"))
      (node (ref "C144") (pin "2") (pinfunction "2_2") (pintype "passive"))
      (node (ref "C145") (pin "1") (pinfunction "1_1") (pintype "passive"))
      (node (ref "C146") (pin "1") (pinfunction "1_1") (pintype "passive"))
      (node (ref "C147") (pin "1") (pinfunction "1_1") (pintype "passive"))
      (node (ref "C148") (pin "2") (pinfunction "2_2") (pintype "passive"))
      (node (ref "C149") (pin "1") (pinfunction "1_1") (pintype "passive"))
      (node (ref "C150") (pin "2") (pinfunction "2_2") (pintype "passive"))
      (node (ref "C151") (pin "2") (pinfunction "2_2") (pintype "passive"))
      (node (ref "C152") (pin "1") (pinfunction "1_1") (pintype "passive"))
      (node (ref "C153") (pin "1") (pinfunction "1_1") (pintype "passive"))
      (node (ref "C154") (pin "1") (pinfunction "1_1") (pintype "passive"))
      (node (ref "C155") (pin "1") (pinfunction "1_1") (pintype "passive"))
      (node (ref "C156") (pin "2") (pinfunction "2_2") (pintype "passive"))
      (node (ref "C157") (pin "1") (pinfunction "1_1") (pintype "passive"))
      (node (ref "C158") (pin "1") (pinfunction "1_1") (pintype "passive"))
      (node (ref "C159") (pin "1") (pinfunction "1_1") (pintype "passive"))
      (node (ref "C160") (pin "1") (pinfunction "1_1") (pintype "passive"))
      (node (ref "C161") (pin "1") (pinfunction "1_1") (pintype "passive"))
      (node (ref "C162") (pin "1") (pinfunction "1_1") (pintype "passive"))
      (node (ref "IC6") (pin "B1") (pinfunction "AFE_GND01_B1") (pintype "power_in"))
      (node (ref "IC6") (pin "B11") (pinfunction "AFE_GND04_B11") (pintype "power_in"))
      (node (ref "IC6") (pin "B13") (pinfunction "AFE_GND05_B13") (pintype "power_in"))
      (node (ref "IC6") (pin "B15") (pinfunction "AFE_GND06_B15") (pintype "power_in"))
      (node (ref "IC6") (pin "B3") (pinfunction "AFE_GND02_B3") (pintype "power_in"))
      (node (ref "IC6") (pin "B5") (pinfunction "AFE_GND03_B5") (pintype "power_in"))
      (node (ref "IC6") (pin "C10") (pinfunction "AFE_GND12_C10") (pintype "power_in"))
      (node (ref "IC6") (pin "C12") (pinfunction "AFE_GND13_C12") (pintype "power_in"))
      (node (ref "IC6") (pin "C14") (pinfunction "AFE_GND14_C14") (pintype "power_in"))
      (node (ref "IC6") (pin "C2") (pinfunction "AFE_GND07_C2") (pintype "power_in"))
      (node (ref "IC6") (pin "C4") (pinfunction "AFE_GND08_C4") (pintype "power_in"))
      (node (ref "IC6") (pin "C6") (pinfunction "AFE_GND09_C6") (pintype "power_in"))
      (node (ref "IC6") (pin "C7") (pinfunction "AFE_GND10_C7") (pintype "power_in"))
      (node (ref "IC6") (pin "C9") (pinfunction "AFE_GND11_C9") (pintype "power_in"))
      (node (ref "IC6") (pin "D10") (pinfunction "AFE_GND17_D10") (pintype "power_in"))
      (node (ref "IC6") (pin "D14") (pinfunction "AFE_GND18_D14") (pintype "power_in"))
      (node (ref "IC6") (pin "D2") (pinfunction "AFE_GND15_D2") (pintype "power_in"))
      (node (ref "IC6") (pin "D5") (pinfunction "VREF_RX_N_D5") (pintype "power_in"))
      (node (ref "IC6") (pin "D6") (pinfunction "AFE_GND16_D6") (pintype "power_in"))
      (node (ref "IC6") (pin "E1") (pinfunction "AFE_GND19_E1") (pintype "power_in"))
      (node (ref "IC6") (pin "E12") (pinfunction "AFE_GND23_E12") (pintype "power_in"))
      (node (ref "IC6") (pin "E15") (pinfunction "AFE_GND24_E15") (pintype "power_in"))
      (node (ref "IC6") (pin "E4") (pinfunction "AFE_GND20_E4") (pintype "power_in"))
      (node (ref "IC6") (pin "E7") (pinfunction "AFE_GND21_E7") (pintype "power_in"))
      (node (ref "IC6") (pin "E9") (pinfunction "AFE_GND22_E9") (pintype "power_in"))
      (node (ref "IC6") (pin "F12") (pinfunction "GND01_F12") (pintype "power_in"))
      (node (ref "IC6") (pin "F3") (pinfunction "AFE_GND25_F3") (pintype "power_in"))
      (node (ref "IC6") (pin "F4") (pinfunction "AFE_GND26_F4") (pintype "power_in"))
      (node (ref "IC6") (pin "F8") (pinfunction "AFE_GND27_F8") (pintype "power_in"))
      (node (ref "IC6") (pin "G11") (pinfunction "GND06_G11") (pintype "power_in"))
      (node (ref "IC6") (pin "G2") (pinfunction "AFE_GND28_G2") (pintype "power_in"))
      (node (ref "IC6") (pin "G3") (pinfunction "GND02_G3") (pintype "power_in"))
      (node (ref "IC6") (pin "G5") (pinfunction "GND03_G5") (pintype "power_in"))
      (node (ref "IC6") (pin "G7") (pinfunction "GND04_G7") (pintype "power_in"))
      (node (ref "IC6") (pin "G9") (pinfunction "GND05_G9") (pintype "power_in"))
      (node (ref "IC6") (pin "H1") (pinfunction "TD1_ANODE_H1") (pintype "power_in"))
      (node (ref "IC6") (pin "H12") (pinfunction "GND08_H12") (pintype "power_in"))
      (node (ref "IC6") (pin "H13") (pinfunction "LLCP_STIN_P_H13") (pintype "power_in"))
      (node (ref "IC6") (pin "H14") (pinfunction "LLCP_DIN_N_H14") (pintype "power_in"))
      (node (ref "IC6") (pin "H15") (pinfunction "LLCP_DIN_P_H15") (pintype "power_in"))
      (node (ref "IC6") (pin "H2") (pinfunction "TD1_CATHODE_H2") (pintype "power_in"))
      (node (ref "IC6") (pin "H8") (pinfunction "GND07_H8") (pintype "power_in"))
      (node (ref "IC6") (pin "J11") (pinfunction "GND14_J11") (pintype "power_in"))
      (node (ref "IC6") (pin "J13") (pinfunction "LLCP_STIN_N_J13") (pintype "power_in"))
      (node (ref "IC6") (pin "J2") (pinfunction "GND09_J2") (pintype "power_in"))
      (node (ref "IC6") (pin "J3") (pinfunction "GND10_J3") (pintype "power_in"))
      (node (ref "IC6") (pin "J5") (pinfunction "GND11_J5") (pintype "power_in"))
      (node (ref "IC6") (pin "J7") (pinfunction "GND12_J7") (pintype "power_in"))
      (node (ref "IC6") (pin "J9") (pinfunction "GND13_J9") (pintype "power_in"))
      (node (ref "IC6") (pin "K12") (pinfunction "GND16_K12") (pintype "power_in"))
      (node (ref "IC6") (pin "K2") (pinfunction "PROG_VDD_K2") (pintype "power_in"))
      (node (ref "IC6") (pin "K8") (pinfunction "GND15_K8") (pintype "power_in"))
      (node (ref "IC6") (pin "L1") (pinfunction "SD_GND1_L1") (pintype "power_in"))
      (node (ref "IC6") (pin "L11") (pinfunction "GND18_L11") (pintype "power_in"))
      (node (ref "IC6") (pin "L6") (pinfunction "SD_GND2_L6") (pintype "power_in"))
      (node (ref "IC6") (pin "L7") (pinfunction "SD_GND3_L7") (pintype "power_in"))
      (node (ref "IC6") (pin "L9") (pinfunction "GND17_L9") (pintype "power_in"))
      (node (ref "IC6") (pin "M2") (pinfunction "SD_GND4_M2") (pintype "power_in"))
      (node (ref "IC6") (pin "N2") (pinfunction "SD_GND5_N2") (pintype "power_in"))
      (node (ref "IC6") (pin "N4") (pinfunction "SD_GND6_N4") (pintype "power_in"))
      (node (ref "IC6") (pin "N6") (pinfunction "SD_GND7_N6") (pintype "power_in"))
      (node (ref "IC6") (pin "P1") (pinfunction "SD_GND8_P1") (pintype "power_in"))
      (node (ref "IC6") (pin "P3") (pinfunction "SD_GND9_P3") (pintype "power_in"))
      (node (ref "IC6") (pin "P5") (pinfunction "SD_GND10_P5") (pintype "power_in"))
      (node (ref "IC7") (pin "2") (pinfunction "GND_2") (pintype "passive"))
      (node (ref "J1") (pin "3") (pinfunction "3_3") (pintype "passive"))
      (node (ref "J1") (pin "5") (pinfunction "5_5") (pintype "passive"))
      (node (ref "J1") (pin "9") (pinfunction "9_9") (pintype "passive"))
      (node (ref "R104") (pin "2") (pinfunction "2_2") (pintype "passive"))
      (node (ref "R105") (pin "2") (pinfunction "2_2") (pintype "passive"))
      (node (ref "R106") (pin "2") (pinfunction "2_2") (pintype "passive"))
      (node (ref "R107") (pin "2") (pinfunction "2_2") (pintype "passive"))
      (node (ref "R108") (pin "2") (pinfunction "2_2") (pintype "passive"))
      (node (ref "R109") (pin "2") (pinfunction "2_2") (pintype "passive"))
      (node (ref "R110") (pin "2") (pinfunction "2_2") (pintype "passive"))
      (node (ref "R111") (pin "2") (pinfunction "2_2") (pintype "passive"))
      (node (ref "R112") (pin "2") (pinfunction "2_2") (pintype "passive"))
      (node (ref "R77") (pin "1") (pinfunction "1_1") (pintype "passive"))
      (node (ref "R85") (pin "2") (pinfunction "2_2") (pintype "passive"))
      (node (ref "R88") (pin "1") (pinfunction "1_1") (pintype "passive"))
      (node (ref "X7") (pin "1") (pinfunction "1_1") (pintype "passive"))
      (node (ref "X7") (pin "12") (pinfunction "12_12") (pintype "passive"))
      (node (ref "X7") (pin "15") (pinfunction "15_15") (pintype "passive"))
      (node (ref "X7") (pin "4") (pinfunction "4_4") (pintype "passive"))
      (node (ref "X7") (pin "7") (pinfunction "7_7") (pintype "passive"))
      (node (ref "X7") (pin "9") (pinfunction "9_9") (pintype "passive"))
      (node (ref "X7") (pin "MP1") (pinfunction "MP1_MP1") (pintype "passive"))
      (node (ref "X7") (pin "MP2") (pinfunction "MP2_MP2") (pintype "passive"))
    )
    (net (code "75") (name "Net-(C126-Pad1)") (class "Default")
      (node (ref "C126") (pin "1") (pinfunction "1_1") (pintype "passive"))
      (node (ref "R82") (pin "1") (pinfunction "1_1") (pintype "passive"))
    )
    (net (code "76") (name "Net-(C132-Pad1)") (class "Default")
      (node (ref "C132") (pin "1") (pinfunction "1_1") (pintype "passive"))
      (node (ref "R86") (pin "1") (pinfunction "1_1") (pintype "passive"))
    )
    (net (code "77") (name "Net-(IC6A-CLKOUT)") (class "Default")
      (node (ref "IC6") (pin "N13") (pinfunction "CLKOUT_N13") (pintype "power_in"))
      (node (ref "R79") (pin "2") (pinfunction "2_2") (pintype "passive"))
    )
    (net (code "78") (name "Net-(IC6A-GPIO_19_{slash}ASLEEP)") (class "Default")
      (node (ref "IC6") (pin "R12") (pinfunction "GPIO_19_/ASLEEP_R12") (pintype "power_in"))
      (node (ref "R76") (pin "2") (pinfunction "2_2") (pintype "passive"))
    )
    (net (code "79") (name "Net-(IC6A-SCAN_MODE_B)") (class "Default")
      (node (ref "IC6") (pin "M13") (pinfunction "SCAN_MODE_B_M13") (pintype "power_in"))
      (node (ref "R87") (pin "1") (pinfunction "1_1") (pintype "passive"))
    )
    (net (code "80") (name "Net-(IC6A-SD1_IMP_CAL_RX)") (class "Default")
      (node (ref "IC6") (pin "K4") (pinfunction "SD1_IMP_CAL_RX_K4") (pintype "power_in"))
      (node (ref "R81") (pin "1") (pinfunction "1_1") (pintype "passive"))
    )
    (net (code "81") (name "Net-(IC6A-SD1_IMP_CAL_TX)") (class "Default")
      (node (ref "IC6") (pin "M4") (pinfunction "SD1_IMP_CAL_TX_M4") (pintype "power_in"))
      (node (ref "R80") (pin "1") (pinfunction "1_1") (pintype "passive"))
    )
    (net (code "82") (name "Net-(IC6B-IREF_TX)") (class "Default")
      (node (ref "IC6") (pin "E8") (pinfunction "IREF_TX_E8") (pintype "power_in"))
      (node (ref "R104") (pin "1") (pinfunction "1_1") (pintype "passive"))
    )
    (net (code "83") (name "Net-(IC7-D)") (class "Default")
      (node (ref "IC7") (pin "5") (pinfunction "D_5") (pintype "passive"))
      (node (ref "R78") (pin "1") (pinfunction "1_1") (pintype "passive"))
      (node (ref "R84") (pin "2") (pinfunction "2_2") (pintype "passive"))
      (node (ref "R85") (pin "1") (pinfunction "1_1") (pintype "passive"))
    )
    (net (code "84") (name "Net-(IC7-Y)") (class "Default")
      (node (ref "C126") (pin "2") (pinfunction "2_2") (pintype "passive"))
      (node (ref "IC7") (pin "4") (pinfunction "Y_4") (pintype "passive"))
      (node (ref "R77") (pin "2") (pinfunction "2_2") (pintype "passive"))
      (node (ref "R78") (pin "2") (pinfunction "2_2") (pintype "passive"))
    )
    (net (code "85") (name "Net-(IC7-Z)") (class "Default")
      (node (ref "C132") (pin "2") (pinfunction "2_2") (pintype "passive"))
      (node (ref "IC7") (pin "3") (pinfunction "Z_3") (pintype "passive"))
      (node (ref "R88") (pin "2") (pinfunction "2_2") (pintype "passive"))
    )
    (net (code "86") (name "Net-(J1-Pad1)") (class "Default")
      (node (ref "J1") (pin "1") (pinfunction "1_1") (pintype "passive"))
      (node (ref "R90") (pin "1") (pinfunction "1_1") (pintype "passive"))
    )
    (net (code "87") (name "Net-(J1-Pad2)") (class "Default")
      (node (ref "J1") (pin "2") (pinfunction "2_2") (pintype "passive"))
      (node (ref "R91") (pin "2") (pinfunction "2_2") (pintype "passive"))
    )
    (net (code "88") (name "Net-(J1-Pad4)") (class "Default")
      (node (ref "J1") (pin "4") (pinfunction "4_4") (pintype "passive"))
      (node (ref "R92") (pin "2") (pinfunction "2_2") (pintype "passive"))
    )
    (net (code "89") (name "Net-(J1-Pad6)") (class "Default")
      (node (ref "J1") (pin "6") (pinfunction "6_6") (pintype "passive"))
      (node (ref "R93") (pin "2") (pinfunction "2_2") (pintype "passive"))
    )
    (net (code "90") (name "Net-(J1-Pad8)") (class "Default")
      (node (ref "J1") (pin "8") (pinfunction "8_8") (pintype "passive"))
      (node (ref "R94") (pin "2") (pinfunction "2_2") (pintype "passive"))
    )
    (net (code "91") (name "Net-(J1-Pad10)") (class "Default")
      (node (ref "J1") (pin "10") (pinfunction "10_10") (pintype "passive"))
      (node (ref "R95") (pin "1") (pinfunction "1_1") (pintype "passive"))
    )
    (net (code "92") (name "Net-(R79-Pad1)") (class "Default")
      (node (ref "R79") (pin "1") (pinfunction "1_1") (pintype "passive"))
      (node (ref "TP1") (pin "1") (pintype "passive"))
    )
    (net (code "93") (name "VCC0P9") (class "Default")
      (node (ref "C139") (pin "2") (pinfunction "2_2") (pintype "passive"))
      (node (ref "C140") (pin "2") (pinfunction "2_2") (pintype "passive"))
      (node (ref "C141") (pin "2") (pinfunction "2_2") (pintype "passive"))
      (node (ref "C142") (pin "2") (pinfunction "2_2") (pintype "passive"))
      (node (ref "C143") (pin "2") (pinfunction "2_2") (pintype "passive"))
      (node (ref "C144") (pin "1") (pinfunction "1_1") (pintype "passive"))
      (node (ref "C148") (pin "1") (pinfunction "1_1") (pintype "passive"))
      (node (ref "C156") (pin "1") (pinfunction "1_1") (pintype "passive"))
      (node (ref "IC6") (pin "G10") (pinfunction "VDD2_G10") (pintype "power_in"))
      (node (ref "IC6") (pin "G6") (pinfunction "VDD1_G6") (pintype "power_in"))
      (node (ref "IC6") (pin "H11") (pinfunction "VDD6_H11") (pintype "power_in"))
      (node (ref "IC6") (pin "H5") (pinfunction "VDD3_H5") (pintype "power_in"))
      (node (ref "IC6") (pin "H7") (pinfunction "VDD4_H7") (pintype "power_in"))
      (node (ref "IC6") (pin "H9") (pinfunction "VDD5_H9") (pintype "power_in"))
      (node (ref "IC6") (pin "J10") (pinfunction "VDD8_J10") (pintype "power_in"))
      (node (ref "IC6") (pin "J6") (pinfunction "VDD7_J6") (pintype "power_in"))
    )
    (net (code "94") (name "VCC0P9_AFE_CVDD") (class "Default")
      (node (ref "C148") (pin "3") (pinfunction "3_3") (pintype "passive"))
      (node (ref "C152") (pin "2") (pinfunction "2_2") (pintype "passive"))
      (node (ref "C153") (pin "2") (pinfunction "2_2") (pintype "passive"))
      (node (ref "C154") (pin "2") (pinfunction "2_2") (pintype "passive"))
      (node (ref "C155") (pin "2") (pinfunction "2_2") (pintype "passive"))
      (node (ref "IC6") (pin "F11") (pinfunction "AFE_CVDD2_F11") (pintype "power_in"))
      (node (ref "IC6") (pin "F5") (pinfunction "AFE_CVDD1_F5") (pintype "power_in"))
    )
    (net (code "95") (name "VCC0P9_AFE_SVDD") (class "Default")
      (node (ref "C149") (pin "2") (pinfunction "2_2") (pintype "passive"))
      (node (ref "C150") (pin "1") (pinfunction "1_1") (pintype "passive"))
      (node (ref "C151") (pin "1") (pinfunction "1_1") (pintype "passive"))
      (node (ref "C156") (pin "3") (pinfunction "3_3") (pintype "passive"))
      (node (ref "C157") (pin "2") (pinfunction "2_2") (pintype "passive"))
      (node (ref "C158") (pin "2") (pinfunction "2_2") (pintype "passive"))
      (node (ref "C159") (pin "2") (pinfunction "2_2") (pintype "passive"))
      (node (ref "C160") (pin "2") (pinfunction "2_2") (pintype "passive"))
      (node (ref "C161") (pin "2") (pinfunction "2_2") (pintype "passive"))
      (node (ref "C162") (pin "2") (pinfunction "2_2") (pintype "passive"))
      (node (ref "IC6") (pin "D3") (pinfunction "VREF_RX_P_D3") (pintype "power_in"))
      (node (ref "IC6") (pin "E10") (pinfunction "AFE_SVDD2_E10") (pintype "power_in"))
      (node (ref "IC6") (pin "E6") (pinfunction "AFE_SVDD1_E6") (pintype "power_in"))
      (node (ref "IC6") (pin "F7") (pinfunction "AFE_SVDD3_F7") (pintype "power_in"))
      (node (ref "IC6") (pin "F9") (pinfunction "AFE_SVDD4_F9") (pintype "power_in"))
    )
    (net (code "96") (name "VCC0P9_SD_SVDD") (class "Default")
      (node (ref "C144") (pin "3") (pinfunction "3_3") (pintype "passive"))
      (node (ref "C145") (pin "2") (pinfunction "2_2") (pintype "passive"))
      (node (ref "C146") (pin "2") (pinfunction "2_2") (pintype "passive"))
      (node (ref "C147") (pin "2") (pinfunction "2_2") (pintype "passive"))
      (node (ref "IC6") (pin "K5") (pinfunction "SD_SVDD1_K5") (pintype "power_in"))
      (node (ref "IC6") (pin "K7") (pinfunction "SD_SVDD2_K7") (pintype "power_in"))
      (node (ref "R81") (pin "2") (pinfunction "2_2") (pintype "passive"))
    )
    (net (code "97") (name "VCC1P8") (class "Default")
      (node (ref "C130") (pin "2") (pinfunction "2_2") (pintype "passive"))
      (node (ref "C131") (pin "2") (pinfunction "2_2") (pintype "passive"))
      (node (ref "C135") (pin "1") (pinfunction "1_1") (pintype "passive"))
      (node (ref "IC6") (pin "K1") (pinfunction "TH_VDD_K1") (pintype "power_in"))
      (node (ref "IC6") (pin "K11") (pinfunction "OVDD2_K11") (pintype "power_in"))
      (node (ref "IC6") (pin "K9") (pinfunction "OVDD1_K9") (pintype "power_in"))
      (node (ref "IC6") (pin "L10") (pinfunction "OVDD3_L10") (pintype "power_in"))
      (node (ref "R72") (pin "1") (pinfunction "1_1") (pintype "passive"))
      (node (ref "R73") (pin "1") (pinfunction "1_1") (pintype "passive"))
      (node (ref "R83") (pin "2") (pinfunction "2_2") (pintype "passive"))
      (node (ref "R87") (pin "2") (pinfunction "2_2") (pintype "passive"))
      (node (ref "R89") (pin "1") (pinfunction "1_1") (pintype "passive"))
      (node (ref "R90") (pin "2") (pinfunction "2_2") (pintype "passive"))
    )
    (net (code "98") (name "VCC1P8_AFE_OTVDD") (class "Default")
      (node (ref "C135") (pin "3") (pinfunction "3_3") (pintype "passive"))
      (node (ref "C136") (pin "2") (pinfunction "2_2") (pintype "passive"))
      (node (ref "C137") (pin "2") (pinfunction "2_2") (pintype "passive"))
      (node (ref "C138") (pin "2") (pinfunction "2_2") (pintype "passive"))
      (node (ref "IC6") (pin "C8") (pinfunction "AFE_OTVDD_C8") (pintype "power_in"))
      (node (ref "IC6") (pin "D11") (pinfunction "AFE_OMVDD_D11") (pintype "power_in"))
    )
    (net (code "99") (name "VCC1P8_AVDD_PLAT") (class "Default")
      (node (ref "C127") (pin "2") (pinfunction "2_2") (pintype "passive"))
      (node (ref "C128") (pin "1") (pinfunction "1_1") (pintype "passive"))
      (node (ref "C129") (pin "1") (pinfunction "1_1") (pintype "passive"))
      (node (ref "IC6") (pin "H3") (pinfunction "AVDD_PLAT_H3") (pintype "power_in"))
      (node (ref "R83") (pin "1") (pinfunction "1_1") (pintype "passive"))
    )
    (net (code "100") (name "VCC1P35") (class "Default")
      (node (ref "C117") (pin "1") (pinfunction "1_1") (pintype "passive"))
      (node (ref "R75") (pin "2") (pinfunction "2_2") (pintype "passive"))
    )
    (net (code "101") (name "VCC1P35_AVDD_SD_PLL") (class "Default")
      (node (ref "C119") (pin "2") (pinfunction "2_2") (pintype "passive"))
      (node (ref "C120") (pin "2") (pinfunction "2_2") (pintype "passive"))
      (node (ref "C124") (pin "1") (pinfunction "1_1") (pintype "passive"))
      (node (ref "IC6") (pin "L3") (pinfunction "AVDD_SD_PLL_L3") (pintype "power_in"))
      (node (ref "R75") (pin "1") (pinfunction "1_1") (pintype "passive"))
    )
    (net (code "102") (name "VCC1P35_SD_XVDD") (class "Default")
      (node (ref "C117") (pin "3") (pinfunction "3_3") (pintype "passive"))
      (node (ref "C121") (pin "2") (pinfunction "2_2") (pintype "passive"))
      (node (ref "C122") (pin "2") (pinfunction "2_2") (pintype "passive"))
      (node (ref "C123") (pin "2") (pinfunction "2_2") (pintype "passive"))
      (node (ref "IC6") (pin "M5") (pinfunction "SD_XVDD1_M5") (pintype "power_in"))
      (node (ref "IC6") (pin "M6") (pinfunction "SD_XVDD2_M6") (pintype "power_in"))
      (node (ref "R80") (pin "2") (pinfunction "2_2") (pintype "passive"))
    )
    (net (code "103") (name "VCC3P3") (class "Default")
      (node (ref "X7") (pin "8") (pinfunction "8_8") (pintype "passive"))
    )
    (net (code "104") (name "VCC3P3_CLK") (class "Default")
      (node (ref "C133") (pin "2") (pinfunction "2_2") (pintype "passive"))
      (node (ref "C134") (pin "1") (pinfunction "1_1") (pintype "passive"))
      (node (ref "IC7") (pin "1") (pinfunction "VCC_1") (pintype "passive"))
    )
    (net (code "105") (name "VCC3P3_M.2") (class "Default")
      (node (ref "R74") (pin "1") (pinfunction "1_1") (pintype "passive"))
    )
    (net (code "106") (name "unconnected-(IC6B-LLCP_DOUT_N-PadG13)") (class "Default")
      (node (ref "IC6") (pin "G13") (pinfunction "LLCP_DOUT_N_G13") (pintype "power_in+no_connect"))
    )
    (net (code "107") (name "unconnected-(IC6B-LLCP_DOUT_P-PadF13)") (class "Default")
      (node (ref "IC6") (pin "F13") (pinfunction "LLCP_DOUT_P_F13") (pintype "power_in+no_connect"))
    )
    (net (code "108") (name "unconnected-(IC6B-LLCP_STOUT_N-PadF14)") (class "Default")
      (node (ref "IC6") (pin "F14") (pinfunction "LLCP_STOUT_N_F14") (pintype "power_in+no_connect"))
    )
    (net (code "109") (name "unconnected-(IC6B-LLCP_STOUT_P-PadF15)") (class "Default")
      (node (ref "IC6") (pin "F15") (pinfunction "LLCP_STOUT_P_F15") (pintype "power_in+no_connect"))
    )
    (net (code "110") (name "unconnected-(IC6B-TX_DET-PadD13)") (class "Default")
      (node (ref "IC6") (pin "D13") (pinfunction "TX_DET_D13") (pintype "power_in+no_connect"))
    )
    (net (code "111") (name "unconnected-(J1-Pad7)") (class "Default")
      (node (ref "J1") (pin "7") (pinfunction "7_7") (pintype "passive+no_connect"))
    )
  )
)
